# energy_meter_blk_-_Copy.net
KiCad netlist of a schematic drawn in Altium Designer
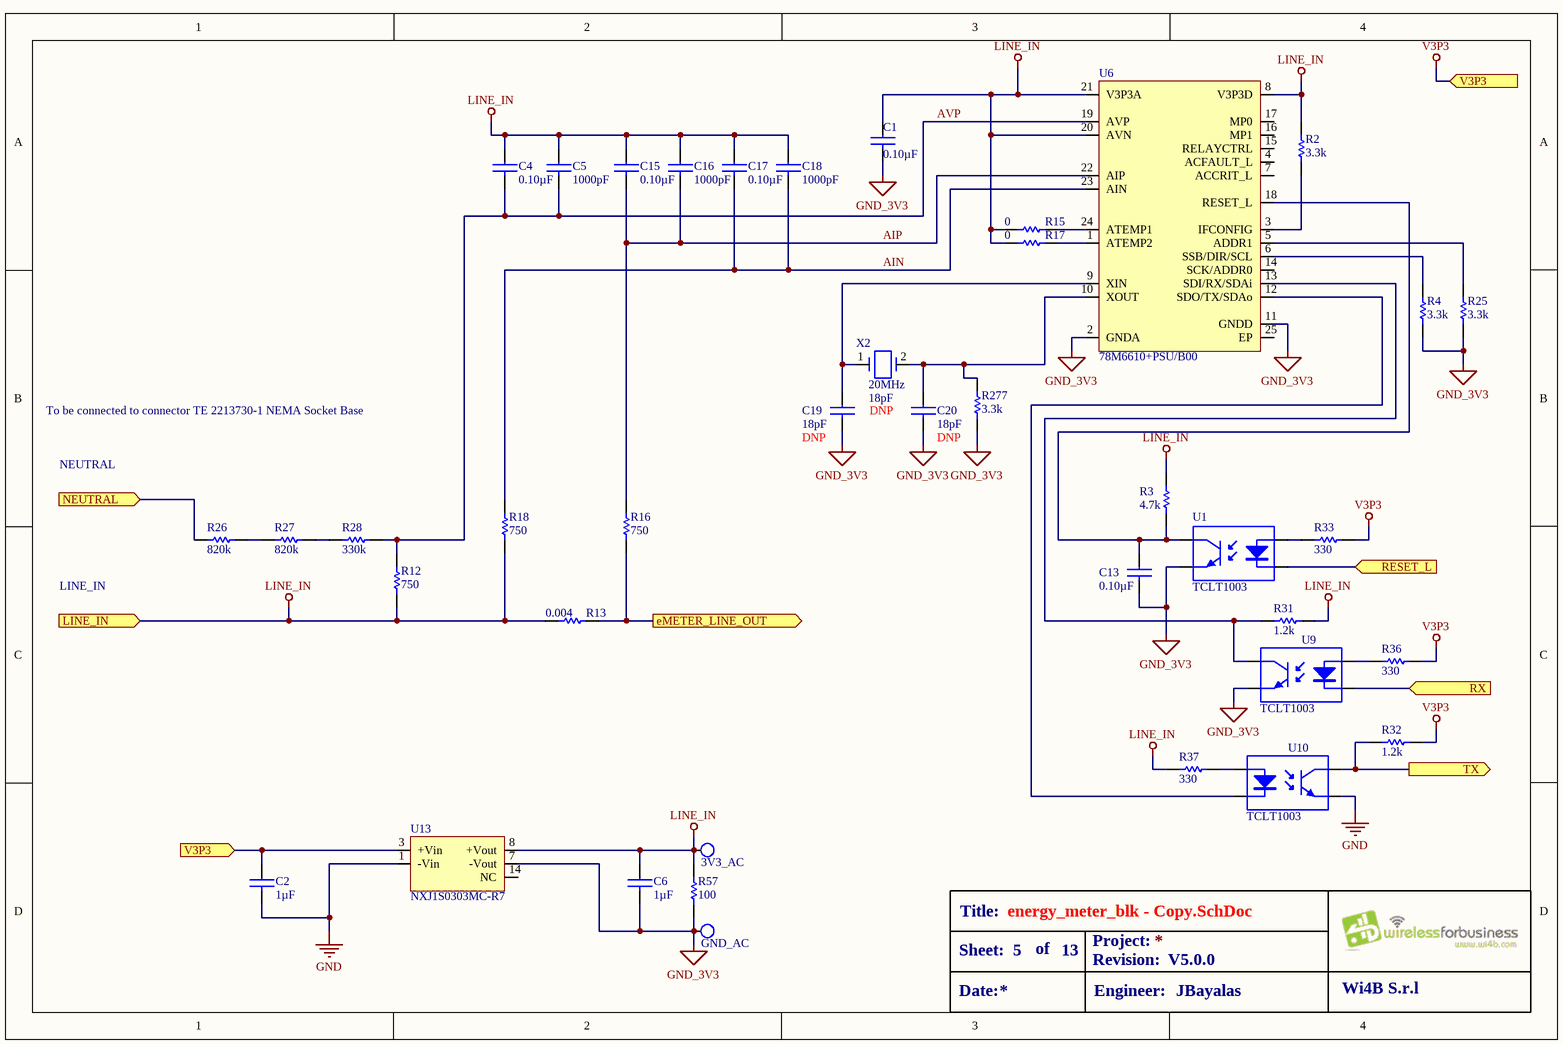
[diagram p0: energy_meter_blk - Copy.SchDoc]

(export (version "E")
  (design (tool "Eeschema 10.0.6"))
  (components
    (comp (ref "3V3_AC")
      (value "TestPad TH")
      (footprint "TestPad TH")
      (libsource (lib "Wilamp-st") (part "TestPad TH"))
    )
    (comp (ref "C1")
      (value "0.10µF")
      (footprint "C0402")
      (description "CAP CER 0.1UF 50V X7R 0402")
      (fields (field (name "MPN") "GRM155R71H104ME14D"))
      (libsource (lib "Capacitor") (part "GRM155R71H104ME14D"))
    )
    (comp (ref "C2")
      (value "1µF")
      (footprint "C0603")
      (description "CAP CER 1UF 16V X7R 0603")
      (fields (field (name "MPN") "GRM188R71C105KA12D"))
      (libsource (lib "Capacitor") (part "GRM188R71C105KA12D"))
    )
    (comp (ref "C4")
      (value "0.10µF")
      (footprint "C0402")
      (description "CAP CER 0.1UF 50V X7R 0402")
      (fields (field (name "MPN") "GRM155R71H104ME14D"))
      (libsource (lib "Capacitor") (part "GRM155R71H104ME14D"))
    )
    (comp (ref "C5")
      (value "1000pF")
      (footprint "C0402")
      (description "CAP CER 1000PF 50V NP0 0402")
      (fields (field (name "MPN") "GRM1555C1H102JA01D"))
      (libsource (lib "Capacitor") (part "GRM1555C1H102JA01D"))
    )
    (comp (ref "C6")
      (value "1µF")
      (footprint "C0603")
      (description "CAP CER 1UF 16V X7R 0603")
      (fields (field (name "MPN") "GRM188R71C105KA12D"))
      (libsource (lib "Capacitor") (part "GRM188R71C105KA12D"))
    )
    (comp (ref "C13")
      (value "0.10µF")
      (footprint "C0402")
      (description "CAP CER 0.1UF 50V X7R 0402")
      (fields (field (name "MPN") "GRM155R71H104ME14D"))
      (libsource (lib "Capacitor") (part "GRM155R71H104ME14D"))
    )
    (comp (ref "C15")
      (value "0.10µF")
      (footprint "C0402")
      (description "CAP CER 0.1UF 50V X7R 0402")
      (fields (field (name "MPN") "GRM155R71H104ME14D"))
      (libsource (lib "Capacitor") (part "GRM155R71H104ME14D"))
    )
    (comp (ref "C16")
      (value "1000pF")
      (footprint "C0402")
      (description "CAP CER 1000PF 50V NP0 0402")
      (fields (field (name "MPN") "GRM1555C1H102JA01D"))
      (libsource (lib "Capacitor") (part "GRM1555C1H102JA01D"))
    )
    (comp (ref "C17")
      (value "0.10µF")
      (footprint "C0402")
      (description "CAP CER 0.1UF 50V X7R 0402")
      (fields (field (name "MPN") "GRM155R71H104ME14D"))
      (libsource (lib "Capacitor") (part "GRM155R71H104ME14D"))
    )
    (comp (ref "C18")
      (value "1000pF")
      (footprint "C0402")
      (description "CAP CER 1000PF 50V NP0 0402")
      (fields (field (name "MPN") "GRM1555C1H102JA01D"))
      (libsource (lib "Capacitor") (part "GRM1555C1H102JA01D"))
    )
    (comp (ref "C19")
      (value "18pF")
      (footprint "C0402")
      (description "CAP CER 18PF 50V NP0 0402")
      (fields (field (name "MPN") "GRM1555C1H180FA01D") (field (name "DNP") "DNP"))
      (libsource (lib "Capacitor") (part "GRM1555C1H180FA01D"))
    )
    (comp (ref "C20")
      (value "18pF")
      (footprint "C0402")
      (description "CAP CER 18PF 50V NP0 0402")
      (fields (field (name "MPN") "GRM1555C1H180FA01D") (field (name "DNP") "DNP"))
      (libsource (lib "Capacitor") (part "GRM1555C1H180FA01D"))
    )
    (comp (ref "GND_AC")
      (value "TestPad TH")
      (footprint "TestPad TH")
      (libsource (lib "Wilamp-st") (part "TestPad TH"))
    )
    (comp (ref "R2")
      (value "3.3k")
      (footprint "R0402")
      (description "RES SMD 3.3K OHM 1% 1/16W 0402")
      (fields (field (name "MPN") "RC0402FR-073K3P"))
      (libsource (lib "Res") (part "RC0402FR-073K3P"))
    )
    (comp (ref "R3")
      (value "4.7k")
      (footprint "R0402")
      (description "RES SMD 4.7K OHM 1% 1/16W 0402")
      (fields (field (name "MPN") "RC0402FR-074K7P"))
      (libsource (lib "Res") (part "RC0402FR-074K7P"))
    )
    (comp (ref "R4")
      (value "3.3k")
      (footprint "R0402")
      (description "RES SMD 3.3K OHM 1% 1/16W 0402")
      (fields (field (name "MPN") "RC0402FR-073K3P"))
      (libsource (lib "Res") (part "RC0402FR-073K3P"))
    )
    (comp (ref "R12")
      (value "750")
      (footprint "R0603")
      (description "RES 750 OHM 1% 1/10W 0603")
      (fields (field (name "MPN") "RC0603FR-07750RL"))
      (libsource (lib "Res") (part "RC0603FR-07750RL"))
    )
    (comp (ref "R13")
      (value "0.004")
      (footprint "R2512")
      (description "RES 0.004 OHM 1% 3W 2512")
      (fields (field (name "MPN") "PA2512FKE7T0R004E"))
      (libsource (lib "Res") (part "PA2512FKE7T0R004E"))
    )
    (comp (ref "R15")
      (value "0")
      (footprint "R0603")
      (description "RES 0 OHM JUMPER 1/10W 0603")
      (fields (field (name "MPN") "RC0603FR-070RL"))
      (libsource (lib "Res") (part "RC0603FR-070RL"))
    )
    (comp (ref "R16")
      (value "750")
      (footprint "R0603")
      (description "RES 750 OHM 1% 1/10W 0603")
      (fields (field (name "MPN") "RC0603FR-07750RL"))
      (libsource (lib "Res") (part "RC0603FR-07750RL"))
    )
    (comp (ref "R17")
      (value "0")
      (footprint "R0603")
      (description "RES 0 OHM JUMPER 1/10W 0603")
      (fields (field (name "MPN") "RC0603FR-070RL"))
      (libsource (lib "Res") (part "RC0603FR-070RL"))
    )
    (comp (ref "R18")
      (value "750")
      (footprint "R0603")
      (description "RES 750 OHM 1% 1/10W 0603")
      (fields (field (name "MPN") "RC0603FR-07750RL"))
      (libsource (lib "Res") (part "RC0603FR-07750RL"))
    )
    (comp (ref "R25")
      (value "3.3k")
      (footprint "R0402")
      (description "RES SMD 3.3K OHM 1% 1/16W 0402")
      (fields (field (name "MPN") "RC0402FR-073K3P"))
      (libsource (lib "Res") (part "RC0402FR-073K3P"))
    )
    (comp (ref "R26")
      (value "820k")
      (footprint "R1206")
      (description "RES 820K OHM 1% 1/4W 1206")
      (fields (field (name "MPN") "RC1206FR-07820KL"))
      (libsource (lib "Res") (part "RC1206FR-07820KL"))
    )
    (comp (ref "R27")
      (value "820k")
      (footprint "R1206")
      (description "RES 820K OHM 1% 1/4W 1206")
      (fields (field (name "MPN") "RC1206FR-07820KL"))
      (libsource (lib "Res") (part "RC1206FR-07820KL"))
    )
    (comp (ref "R28")
      (value "330k")
      (footprint "R1206")
      (description "RES 330K OHM 1% 1/4W 1206")
      (fields (field (name "MPN") "RC1206FR-07330KL"))
      (libsource (lib "Res") (part "RC1206FR-07330KL"))
    )
    (comp (ref "R31")
      (value "1.2k")
      (footprint "RESC1005X40N")
      (description "RES SMD 1.2K OHM 1% 1/16W 0402")
      (fields (field (name "MPN") "RC0402FR-071K2L"))
      (libsource (lib "Res") (part "RC0402FR-071K2L"))
    )
    (comp (ref "R32")
      (value "1.2k")
      (footprint "RESC1005X40N")
      (description "RES SMD 1.2K OHM 1% 1/16W 0402")
      (fields (field (name "MPN") "RC0402FR-071K2L"))
      (libsource (lib "Res") (part "RC0402FR-071K2L"))
    )
    (comp (ref "R33")
      (value "330")
      (footprint "R0402")
      (description "RES SMD 330 OHM 1% 1/16W 0402")
      (fields (field (name "MPN") "RC0402FR-07330RL"))
      (libsource (lib "Res") (part "RC0402FR-07330RL"))
    )
    (comp (ref "R36")
      (value "330")
      (footprint "R0402")
      (description "RES SMD 330 OHM 1% 1/16W 0402")
      (fields (field (name "MPN") "RC0402FR-07330RL"))
      (libsource (lib "Res") (part "RC0402FR-07330RL"))
    )
    (comp (ref "R37")
      (value "330")
      (footprint "R0402")
      (description "RES SMD 330 OHM 1% 1/16W 0402")
      (fields (field (name "MPN") "RC0402FR-07330RL"))
      (libsource (lib "Res") (part "RC0402FR-07330RL"))
    )
    (comp (ref "R57")
      (value "100")
      (footprint "R1206")
      (description "RES 100 OHM 5% 1/4W 1206")
      (fields (field (name "MPN") "RC1206JR-07100RL"))
      (libsource (lib "Res") (part "RC1206JR-07100RL"))
    )
    (comp (ref "R277")
      (value "3.3k")
      (footprint "R0402")
      (description "RES SMD 3.3K OHM 1% 1/16W 0402")
      (fields (field (name "MPN") "RC0402FR-073K3P"))
      (libsource (lib "Res") (part "RC0402FR-073K3P"))
    )
    (comp (ref "U1")
      (value "TCLT1003")
      (footprint "SOP-4L")
      (description "OPTOISOLATR 5KV TRANSISTOR 4-SOP")
      (fields (field (name "MPN") "TCLT1003"))
      (libsource (lib "IC") (part "TCLT1003"))
    )
    (comp (ref "U6")
      (value "78M6610+PSU/B00")
      (footprint "QFN-24 (4X4mm)")
      (description "IC ENERGY MEASURMENT 1PH 24TQFN")
      (fields
        (field (name "MANUFACTURER") "Maxim Integrated")
        (field (name "MANUFACTURER PART NUMBER") "78M6610+PSU/B00")
      )
      (libsource (lib "Wilamp") (part "78M6610+PSU/B00"))
    )
    (comp (ref "U9")
      (value "TCLT1003")
      (footprint "SOP-4L")
      (description "OPTOISOLATR 5KV TRANSISTOR 4-SOP")
      (fields (field (name "MPN") "TCLT1003"))
      (libsource (lib "IC") (part "TCLT1003"))
    )
    (comp (ref "U10")
      (value "TCLT1003")
      (footprint "SOP-4L")
      (description "OPTOISOLATR 5KV TRANSISTOR 4-SOP")
      (fields (field (name "MPN") "TCLT1003"))
      (libsource (lib "IC") (part "TCLT1003"))
    )
    (comp (ref "U13")
      (value "NXJ1S0303MC-R7")
      (footprint "NXJ1S0303MC-R7")
      (description "Isolated DC/DC Converters 1W 3.3Vin 3.3Vout 333mA SM")
      (fields (field (name "MPN") "NXJ1S0303MC-R7"))
      (libsource (lib "IC") (part "NXJ1S0303MC-R7"))
    )
    (comp (ref "X2")
      (value "ABLS7M-20.000MHZ-B-2-T")
      (footprint "ABLS7M (crystal)")
      (description "CRYSTAL 20.000 MHZ 18PF SMT")
      (fields
        (field (name "MANUFACTURER") "Abracon LLC")
        (field (name "FREQUENCY") "20MHz")
        (field (name "LOAD CAPACITANCE") "18pF")
        (field (name "DNP") "DNP")
      )
      (libsource (lib "Wilamp") (part "ABLS7M-20.000MHZ-B-2-T"))
    )
  )
  (nets
    (net (code "1") (name "/AIN") (class "Default")
      (node (ref "C17") (pin "2") (pinfunction "2_2") (pintype "passive"))
      (node (ref "C18") (pin "2") (pinfunction "2_2") (pintype "passive"))
      (node (ref "R18") (pin "2") (pinfunction "2_2") (pintype "passive"))
      (node (ref "U6") (pin "23") (pinfunction "AIN_23") (pintype "passive"))
    )
    (net (code "2") (name "/AIP") (class "Default")
      (node (ref "C15") (pin "2") (pinfunction "2_2") (pintype "passive"))
      (node (ref "C16") (pin "2") (pinfunction "2_2") (pintype "passive"))
      (node (ref "R16") (pin "2") (pinfunction "2_2") (pintype "passive"))
      (node (ref "U6") (pin "22") (pinfunction "AIP_22") (pintype "passive"))
    )
    (net (code "3") (name "/AVP") (class "Default")
      (node (ref "C4") (pin "2") (pinfunction "2_2") (pintype "passive"))
      (node (ref "C5") (pin "2") (pinfunction "2_2") (pintype "passive"))
      (node (ref "R12") (pin "2") (pinfunction "2_2") (pintype "passive"))
      (node (ref "R28") (pin "2") (pinfunction "2_2") (pintype "passive"))
      (node (ref "U6") (pin "19") (pinfunction "AVP_19") (pintype "passive"))
    )
    (net (code "4") (name "/NEUTRAL") (class "Default")
      (node (ref "R26") (pin "1") (pinfunction "1_1") (pintype "passive"))
    )
    (net (code "5") (name "/RESET_L") (class "Default")
      (node (ref "U1") (pin "2") (pinfunction "K_2") (pintype "passive"))
    )
    (net (code "6") (name "/RX") (class "Default")
      (node (ref "U9") (pin "2") (pinfunction "K_2") (pintype "passive"))
    )
    (net (code "7") (name "/TX") (class "Default")
      (node (ref "R32") (pin "1") (pinfunction "1_1") (pintype "passive"))
      (node (ref "U10") (pin "4") (pinfunction "A/K_4") (pintype "passive"))
    )
    (net (code "8") (name "/eMETER_LINE_OUT") (class "Default")
      (node (ref "R13") (pin "2") (pinfunction "2_2") (pintype "passive"))
      (node (ref "R16") (pin "1") (pinfunction "1_1") (pintype "passive"))
    )
    (net (code "9") (name "GND") (class "Default")
      (node (ref "C2") (pin "2") (pinfunction "2_2") (pintype "passive"))
      (node (ref "U10") (pin "3") (pinfunction "A/K_3") (pintype "passive"))
      (node (ref "U13") (pin "1") (pinfunction "-Vin_1") (pintype "passive"))
    )
    (net (code "10") (name "GND_3V3") (class "Default")
      (node (ref "C1") (pin "2") (pinfunction "2_2") (pintype "passive"))
      (node (ref "C13") (pin "2") (pinfunction "2_2") (pintype "passive"))
      (node (ref "C19") (pin "2") (pinfunction "2_2") (pintype "passive"))
      (node (ref "C20") (pin "2") (pinfunction "2_2") (pintype "passive"))
      (node (ref "C6") (pin "2") (pinfunction "2_2") (pintype "passive"))
      (node (ref "GND_AC") (pin "1") (pinfunction "1_1") (pintype "passive"))
      (node (ref "R25") (pin "1") (pinfunction "1_1") (pintype "passive"))
      (node (ref "R277") (pin "1") (pinfunction "1_1") (pintype "passive"))
      (node (ref "R4") (pin "1") (pinfunction "1_1") (pintype "passive"))
      (node (ref "R57") (pin "1") (pinfunction "1_1") (pintype "passive"))
      (node (ref "U1") (pin "3") (pinfunction "A/K_3") (pintype "passive"))
      (node (ref "U13") (pin "7") (pinfunction "-Vout_7") (pintype "passive"))
      (node (ref "U6") (pin "11") (pinfunction "GNDD_11") (pintype "passive"))
      (node (ref "U6") (pin "2") (pinfunction "GNDA_2") (pintype "passive"))
      (node (ref "U9") (pin "3") (pinfunction "A/K_3") (pintype "passive"))
    )
    (net (code "11") (name "LINE_IN") (class "Default")
      (node (ref "3V3_AC") (pin "1") (pinfunction "1_1") (pintype "passive"))
      (node (ref "C1") (pin "1") (pinfunction "1_1") (pintype "passive"))
      (node (ref "C15") (pin "1") (pinfunction "1_1") (pintype "passive"))
      (node (ref "C16") (pin "1") (pinfunction "1_1") (pintype "passive"))
      (node (ref "C17") (pin "1") (pinfunction "1_1") (pintype "passive"))
      (node (ref "C18") (pin "1") (pinfunction "1_1") (pintype "passive"))
      (node (ref "C4") (pin "1") (pinfunction "1_1") (pintype "passive"))
      (node (ref "C5") (pin "1") (pinfunction "1_1") (pintype "passive"))
      (node (ref "C6") (pin "1") (pinfunction "1_1") (pintype "passive"))
      (node (ref "R12") (pin "1") (pinfunction "1_1") (pintype "passive"))
      (node (ref "R13") (pin "1") (pinfunction "1_1") (pintype "passive"))
      (node (ref "R15") (pin "1") (pinfunction "1_1") (pintype "passive"))
      (node (ref "R17") (pin "1") (pinfunction "1_1") (pintype "passive"))
      (node (ref "R18") (pin "1") (pinfunction "1_1") (pintype "passive"))
      (node (ref "R2") (pin "2") (pinfunction "2_2") (pintype "passive"))
      (node (ref "R3") (pin "2") (pinfunction "2_2") (pintype "passive"))
      (node (ref "R31") (pin "2") (pinfunction "2_2") (pintype "passive"))
      (node (ref "R37") (pin "1") (pinfunction "1_1") (pintype "passive"))
      (node (ref "R57") (pin "2") (pinfunction "2_2") (pintype "passive"))
      (node (ref "U13") (pin "8") (pinfunction "+Vout_8") (pintype "passive"))
      (node (ref "U6") (pin "20") (pinfunction "AVN_20") (pintype "passive"))
      (node (ref "U6") (pin "21") (pinfunction "V3P3A_21") (pintype "passive"))
      (node (ref "U6") (pin "8") (pinfunction "V3P3D_8") (pintype "passive"))
    )
    (net (code "12") (name "Net-(R26-Pad2)") (class "Default")
      (node (ref "R26") (pin "2") (pinfunction "2_2") (pintype "passive"))
      (node (ref "R27") (pin "1") (pinfunction "1_1") (pintype "passive"))
    )
    (net (code "13") (name "Net-(R27-Pad2)") (class "Default")
      (node (ref "R27") (pin "2") (pinfunction "2_2") (pintype "passive"))
      (node (ref "R28") (pin "1") (pinfunction "1_1") (pintype "passive"))
    )
    (net (code "14") (name "Net-(U1-A)") (class "Default")
      (node (ref "R33") (pin "1") (pinfunction "1_1") (pintype "passive"))
      (node (ref "U1") (pin "1") (pinfunction "A_1") (pintype "passive"))
    )
    (net (code "15") (name "Net-(U6-ADDR1)") (class "Default")
      (node (ref "R25") (pin "2") (pinfunction "2_2") (pintype "passive"))
      (node (ref "U6") (pin "5") (pinfunction "ADDR1_5") (pintype "passive"))
    )
    (net (code "16") (name "Net-(U6-ATEMP1)") (class "Default")
      (node (ref "R15") (pin "2") (pinfunction "2_2") (pintype "passive"))
      (node (ref "U6") (pin "24") (pinfunction "ATEMP1_24") (pintype "passive"))
    )
    (net (code "17") (name "Net-(U6-ATEMP2)") (class "Default")
      (node (ref "R17") (pin "2") (pinfunction "2_2") (pintype "passive"))
      (node (ref "U6") (pin "1") (pinfunction "ATEMP2_1") (pintype "passive"))
    )
    (net (code "18") (name "Net-(U6-IFCONFIG)") (class "Default")
      (node (ref "R2") (pin "1") (pinfunction "1_1") (pintype "passive"))
      (node (ref "U6") (pin "3") (pinfunction "IFCONFIG_3") (pintype "passive"))
    )
    (net (code "19") (name "Net-(U6-RESET_L)") (class "Default")
      (node (ref "C13") (pin "1") (pinfunction "1_1") (pintype "passive"))
      (node (ref "R3") (pin "1") (pinfunction "1_1") (pintype "passive"))
      (node (ref "U1") (pin "4") (pinfunction "A/K_4") (pintype "passive"))
      (node (ref "U6") (pin "18") (pinfunction "RESET_L_18") (pintype "passive"))
    )
    (net (code "20") (name "Net-(U6-SDI{slash}RX{slash}SDAi)") (class "Default")
      (node (ref "R31") (pin "1") (pinfunction "1_1") (pintype "passive"))
      (node (ref "U6") (pin "13") (pinfunction "SDI/RX/SDAi_13") (pintype "passive"))
      (node (ref "U9") (pin "4") (pinfunction "A/K_4") (pintype "passive"))
    )
    (net (code "21") (name "Net-(U6-SSB{slash}DIR{slash}SCL)") (class "Default")
      (node (ref "R4") (pin "2") (pinfunction "2_2") (pintype "passive"))
      (node (ref "U6") (pin "6") (pinfunction "SSB/DIR/SCL_6") (pintype "passive"))
    )
    (net (code "22") (name "Net-(U6-XIN)") (class "Default")
      (node (ref "C19") (pin "1") (pinfunction "1_1") (pintype "passive"))
      (node (ref "U6") (pin "9") (pinfunction "XIN_9") (pintype "passive"))
      (node (ref "X2") (pin "1") (pinfunction "1_1") (pintype "passive"))
    )
    (net (code "23") (name "Net-(U6-XOUT)") (class "Default")
      (node (ref "C20") (pin "1") (pinfunction "1_1") (pintype "passive"))
      (node (ref "R277") (pin "2") (pinfunction "2_2") (pintype "passive"))
      (node (ref "U6") (pin "10") (pinfunction "XOUT_10") (pintype "passive"))
      (node (ref "X2") (pin "2") (pinfunction "2_2") (pintype "passive"))
    )
    (net (code "24") (name "Net-(U9-A)") (class "Default")
      (node (ref "R36") (pin "1") (pinfunction "1_1") (pintype "passive"))
      (node (ref "U9") (pin "1") (pinfunction "A_1") (pintype "passive"))
    )
    (net (code "25") (name "Net-(U10-A)") (class "Default")
      (node (ref "R37") (pin "2") (pinfunction "2_2") (pintype "passive"))
      (node (ref "U10") (pin "1") (pinfunction "A_1") (pintype "passive"))
    )
    (net (code "26") (name "Net-(U10-K)") (class "Default")
      (node (ref "U10") (pin "2") (pinfunction "K_2") (pintype "passive"))
      (node (ref "U6") (pin "12") (pinfunction "SDO/TX/SDAo_12") (pintype "passive"))
    )
    (net (code "27") (name "V3P3") (class "Default")
      (node (ref "C2") (pin "1") (pinfunction "1_1") (pintype "passive"))
      (node (ref "R32") (pin "2") (pinfunction "2_2") (pintype "passive"))
      (node (ref "R33") (pin "2") (pinfunction "2_2") (pintype "passive"))
      (node (ref "R36") (pin "2") (pinfunction "2_2") (pintype "passive"))
      (node (ref "U13") (pin "3") (pinfunction "+Vin_3") (pintype "passive"))
    )
    (net (code "28") (name "unconnected-(U6-ACCRIT_L-Pad7)") (class "Default")
      (node (ref "U6") (pin "7") (pinfunction "ACCRIT_L_7") (pintype "passive"))
    )
    (net (code "29") (name "unconnected-(U6-ACFAULT_L-Pad4)") (class "Default")
      (node (ref "U6") (pin "4") (pinfunction "ACFAULT_L_4") (pintype "passive"))
    )
    (net (code "30") (name "unconnected-(U6-EP-Pad25)") (class "Default")
      (node (ref "U6") (pin "25") (pinfunction "EP_25") (pintype "passive"))
    )
    (net (code "31") (name "unconnected-(U6-MP0-Pad17)") (class "Default")
      (node (ref "U6") (pin "17") (pinfunction "MP0_17") (pintype "passive"))
    )
    (net (code "32") (name "unconnected-(U6-MP1-Pad16)") (class "Default")
      (node (ref "U6") (pin "16") (pinfunction "MP1_16") (pintype "passive"))
    )
    (net (code "33") (name "unconnected-(U6-RELAYCTRL-Pad15)") (class "Default")
      (node (ref "U6") (pin "15") (pinfunction "RELAYCTRL_15") (pintype "passive"))
    )
    (net (code "34") (name "unconnected-(U6-SCK{slash}ADDR0-Pad14)") (class "Default")
      (node (ref "U6") (pin "14") (pinfunction "SCK/ADDR0_14") (pintype "passive"))
    )
    (net (code "35") (name "unconnected-(U13-NC-Pad14)") (class "Default")
      (node (ref "U13") (pin "14") (pinfunction "NC_14") (pintype "passive"))
    )
  )
)
